# Almazny_top.net
KiCad netlist of a schematic drawn in Altium Designer
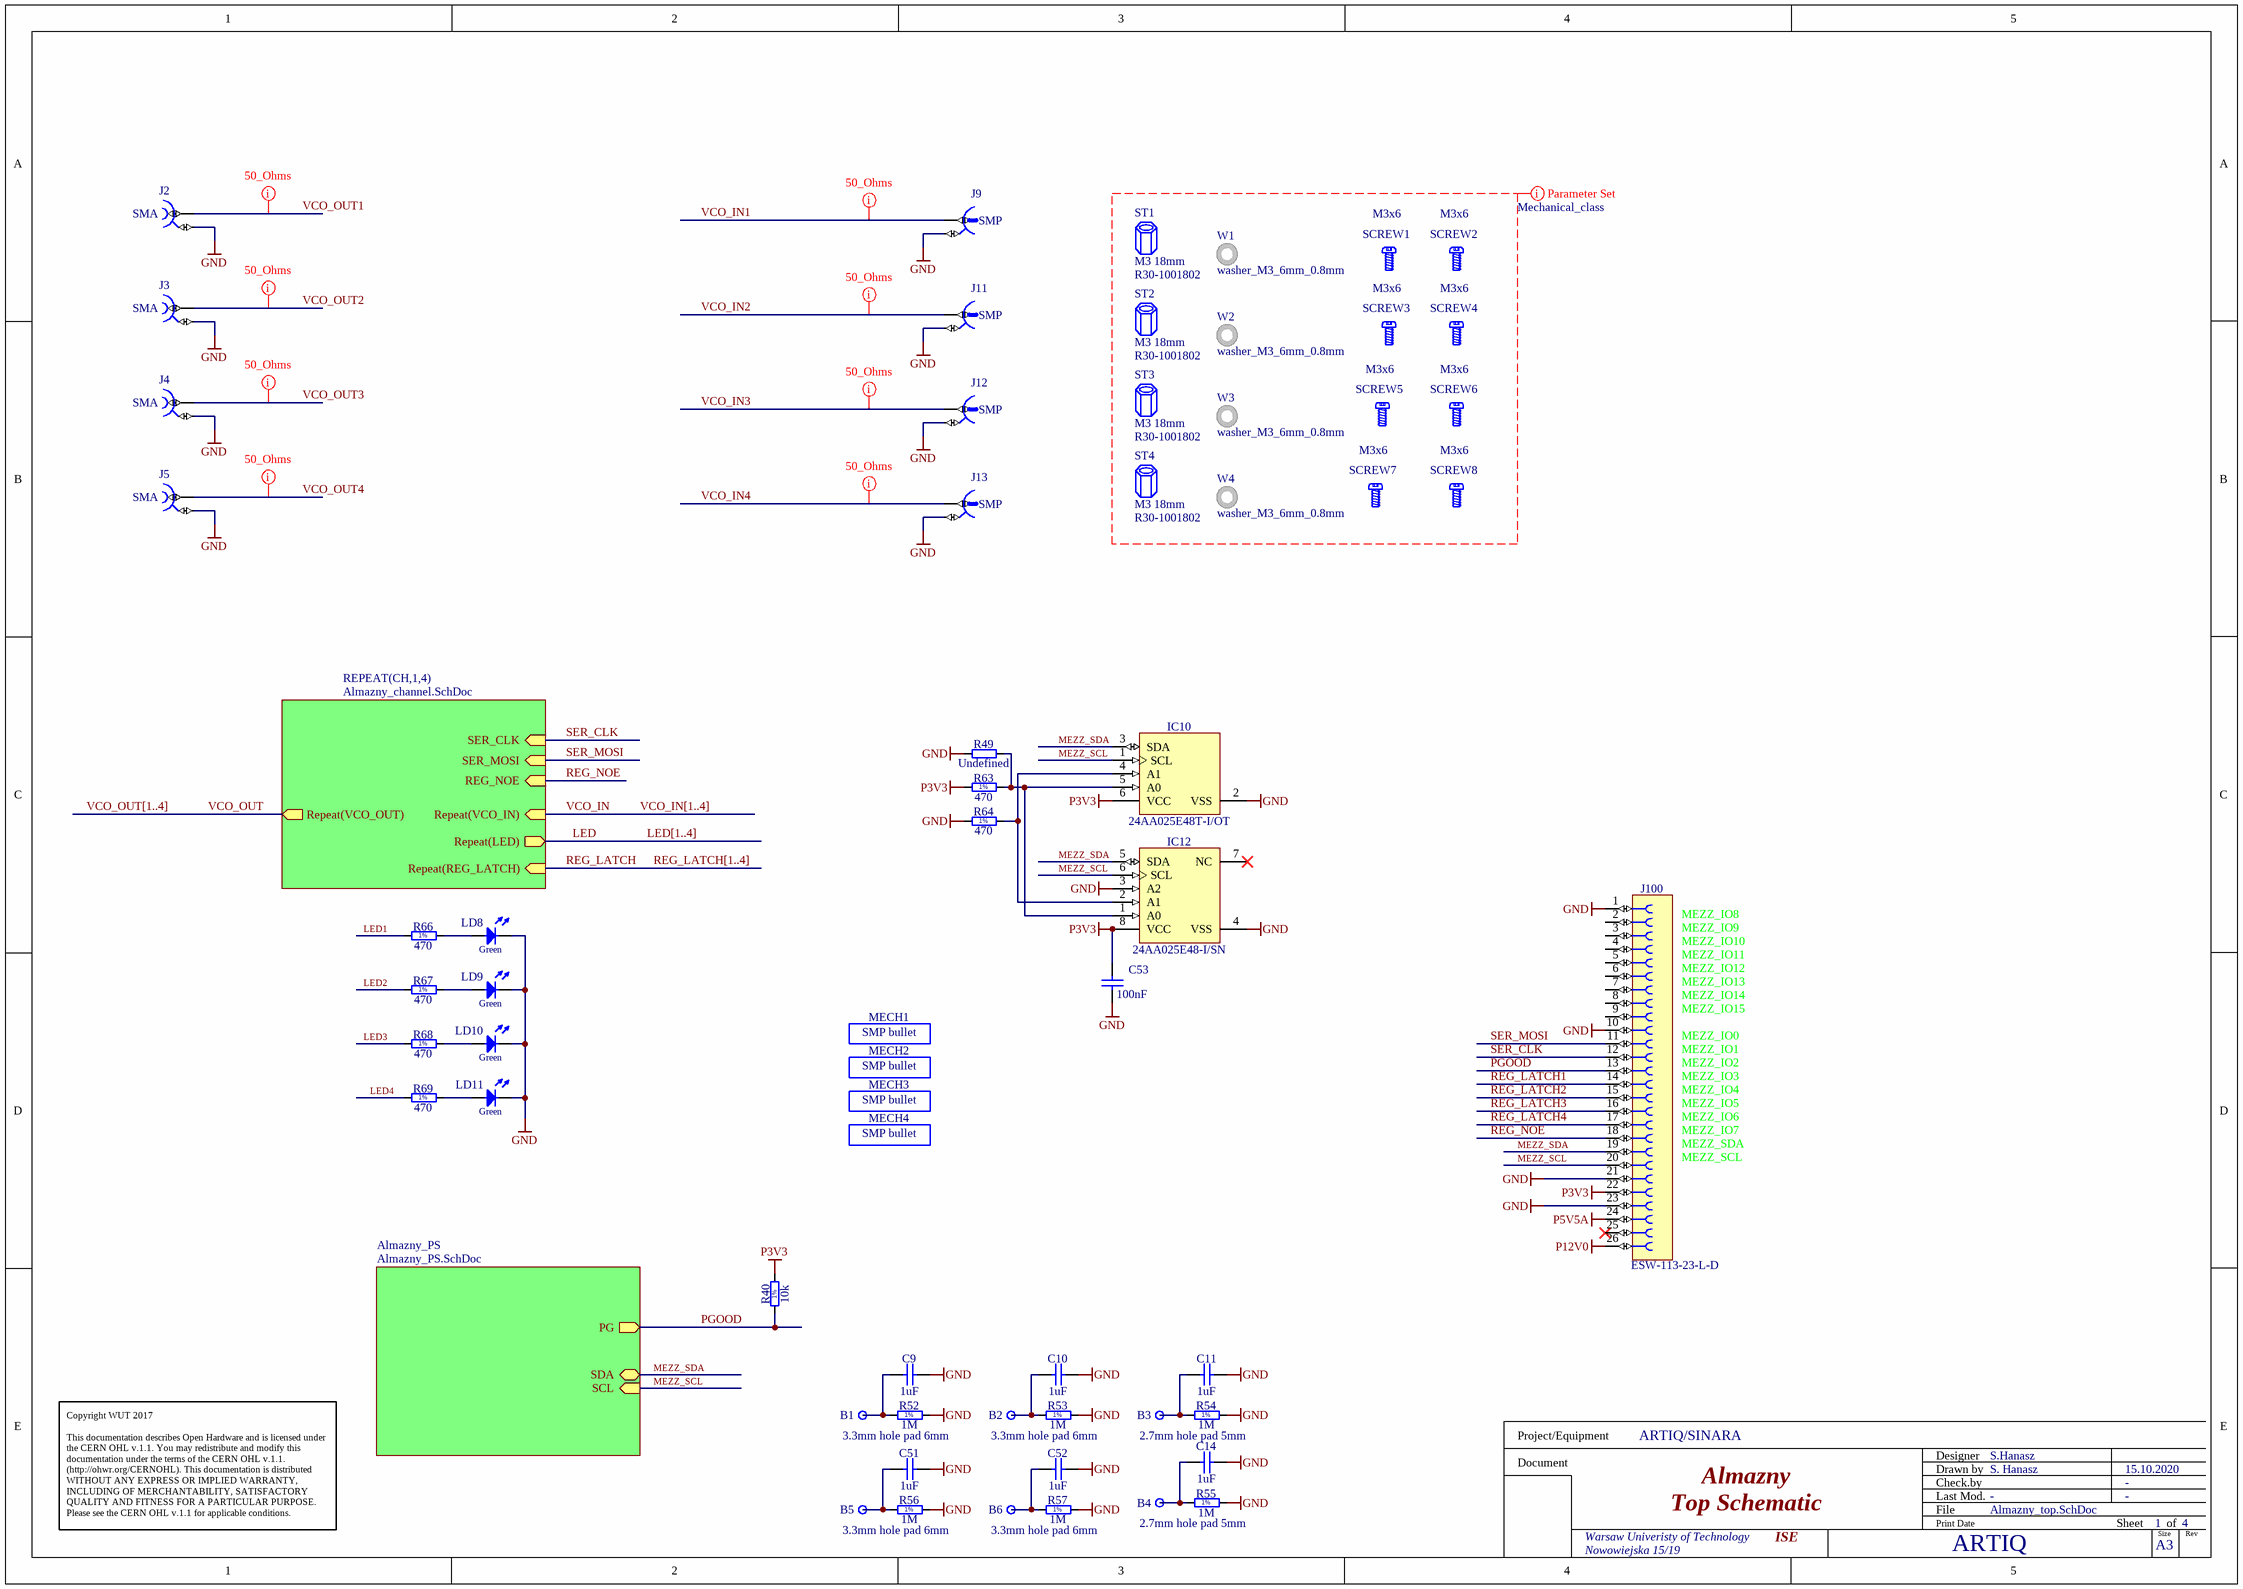
[diagram p0: Almazny_top.SchDoc]

(export (version "E")
  (design (tool "Eeschema 10.0.6"))
  (components
    (comp (ref "B1")
      (value "3.3mm hole pad 6mm")
      (footprint "MTG330_600")
      (fields (field (name "PART NUMBER") "PLATED_HOLE3.3_PAD560") (field (name "AUTHOR") "CERN DEM JMW"))
      (libsource (lib "AlmaznyLib") (part "Hole_3_3mm"))
    )
    (comp (ref "B2")
      (value "3.3mm hole pad 6mm")
      (footprint "MTG330_600")
      (fields (field (name "PART NUMBER") "PLATED_HOLE3.3_PAD560") (field (name "AUTHOR") "CERN DEM JMW"))
      (libsource (lib "AlmaznyLib") (part "Hole_3_3mm"))
    )
    (comp (ref "B3")
      (value "2.7mm hole pad 5mm")
      (footprint "MTG270_500")
      (fields (field (name "PART NUMBER") "PLATED_HOLE2.7_PAD5.0") (field (name "AUTHOR") "CERN DEM JMW"))
      (libsource (lib "AlmaznyLib") (part "Hole_2_7mm"))
    )
    (comp (ref "B4")
      (value "2.7mm hole pad 5mm")
      (footprint "MTG270_500")
      (fields (field (name "PART NUMBER") "PLATED_HOLE2.7_PAD5.0") (field (name "AUTHOR") "CERN DEM JMW"))
      (libsource (lib "AlmaznyLib") (part "Hole_2_7mm"))
    )
    (comp (ref "B5")
      (value "3.3mm hole pad 6mm")
      (footprint "MTG330_600")
      (fields (field (name "PART NUMBER") "PLATED_HOLE3.3_PAD560") (field (name "AUTHOR") "CERN DEM JMW"))
      (libsource (lib "AlmaznyLib") (part "Hole_3_3mm"))
    )
    (comp (ref "B6")
      (value "3.3mm hole pad 6mm")
      (footprint "MTG330_600")
      (fields (field (name "PART NUMBER") "PLATED_HOLE3.3_PAD560") (field (name "AUTHOR") "CERN DEM JMW"))
      (libsource (lib "AlmaznyLib") (part "Hole_3_3mm"))
    )
    (comp (ref "C9")
      (value "1uF")
      (footprint "CAPC3216X140N")
      (description "Non-polarised capacitor")
      (fields
        (field (name "PART NUMBER") "CC1206_1UF_50V_10%_X7R")
        (field (name "VOLTAGE") "50V")
        (field (name "AUTHOR") "CERN DEM JLC")
      )
      (libsource (lib "Capacitors") (part "Capacitor - non polarized"))
    )
    (comp (ref "C10")
      (value "1uF")
      (footprint "CAPC3216X140N")
      (description "Non-polarised capacitor")
      (fields
        (field (name "PART NUMBER") "CC1206_1UF_50V_10%_X7R")
        (field (name "VOLTAGE") "50V")
        (field (name "AUTHOR") "CERN DEM JLC")
      )
      (libsource (lib "Capacitors") (part "Capacitor - non polarized"))
    )
    (comp (ref "C11")
      (value "1uF")
      (footprint "CAPC3216X140N")
      (description "Non-polarised capacitor")
      (fields
        (field (name "PART NUMBER") "CC1206_1UF_50V_10%_X7R")
        (field (name "VOLTAGE") "50V")
        (field (name "AUTHOR") "CERN DEM JLC")
      )
      (libsource (lib "Capacitors") (part "Capacitor - non polarized"))
    )
    (comp (ref "C14")
      (value "1uF")
      (footprint "CAPC3216X140N")
      (description "Non-polarised capacitor")
      (fields
        (field (name "PART NUMBER") "CC1206_1UF_50V_10%_X7R")
        (field (name "VOLTAGE") "50V")
        (field (name "AUTHOR") "CERN DEM JLC")
      )
      (libsource (lib "Capacitors") (part "Capacitor - non polarized"))
    )
    (comp (ref "C51")
      (value "1uF")
      (footprint "CAPC3216X140N")
      (description "Non-polarised capacitor")
      (fields
        (field (name "PART NUMBER") "CC1206_1UF_50V_10%_X7R")
        (field (name "VOLTAGE") "50V")
        (field (name "AUTHOR") "CERN DEM JLC")
      )
      (libsource (lib "Capacitors") (part "Capacitor - non polarized"))
    )
    (comp (ref "C52")
      (value "1uF")
      (footprint "CAPC3216X140N")
      (description "Non-polarised capacitor")
      (fields
        (field (name "PART NUMBER") "CC1206_1UF_50V_10%_X7R")
        (field (name "VOLTAGE") "50V")
        (field (name "AUTHOR") "CERN DEM JLC")
      )
      (libsource (lib "Capacitors") (part "Capacitor - non polarized"))
    )
    (comp (ref "C53")
      (value "100nF")
      (footprint "CAPC1005X55N")
      (description "Non-polarised capacitor")
      (fields
        (field (name "PART NUMBER") "CC0402_100NF_16V_10%_X5R")
        (field (name "VOLTAGE") "16V")
        (field (name "AUTHOR") "CERN DEM JLC")
      )
      (libsource (lib "Capacitors") (part "Capacitor - non polarized"))
    )
    (comp (ref "IC10")
      (value "24AA025E48T-I/OT")
      (footprint "SOT95P280X145-6N")
      (description "1.7V-5.5V, 2K I2C Serial EEPROM With EUI-48 Node Identity")
      (fields (field (name "MANUFACTURER") "MICROCHIP TECHNOLOGY") (field (name "AUTHOR") "CERN DEM BC"))
      (libsource (lib "ICs And Semiconductors") (part "24AA025E48T-I/OT"))
    )
    (comp (ref "IC12")
      (value "24AA025E48-I/SN")
      (footprint "SOIC127P600X175-8N")
      (description "1.7V-5.5V, 2K I2C™ Serial EEPROMs with EUI-48™ Node Identity")
      (fields (field (name "MANUFACTURER") "MICROCHIP TECHNOLOGY") (field (name "AUTHOR") "CERN DEM MR"))
      (libsource (lib "ICs And Semiconductors") (part "24AA025E48-I/SN"))
    )
    (comp (ref "J2")
      (value "SMA")
      (footprint "TELEGARTNER_J01151A0451")
      (fields
        (field (name "PART NUMBER") "TELEGARTNER_J01151A0451")
        (field (name "MANUFACTURER") "TELEGARTNER")
        (field (name "MANUFACTURER PART NUMBER") "J01151A0451")
        (field (name "AUTHOR") "CERN DEM JLC")
      )
      (libsource (lib "Connectors") (part "Coax_1Female_1Shield"))
    )
    (comp (ref "J3")
      (value "SMA")
      (footprint "TELEGARTNER_J01151A0451")
      (fields
        (field (name "PART NUMBER") "TELEGARTNER_J01151A0451")
        (field (name "MANUFACTURER") "TELEGARTNER")
        (field (name "MANUFACTURER PART NUMBER") "J01151A0451")
        (field (name "AUTHOR") "CERN DEM JLC")
      )
      (libsource (lib "Connectors") (part "Coax_1Female_1Shield"))
    )
    (comp (ref "J4")
      (value "SMA")
      (footprint "TELEGARTNER_J01151A0451")
      (fields
        (field (name "PART NUMBER") "TELEGARTNER_J01151A0451")
        (field (name "MANUFACTURER") "TELEGARTNER")
        (field (name "MANUFACTURER PART NUMBER") "J01151A0451")
        (field (name "AUTHOR") "CERN DEM JLC")
      )
      (libsource (lib "Connectors") (part "Coax_1Female_1Shield"))
    )
    (comp (ref "J5")
      (value "SMA")
      (footprint "TELEGARTNER_J01151A0451")
      (fields
        (field (name "PART NUMBER") "TELEGARTNER_J01151A0451")
        (field (name "MANUFACTURER") "TELEGARTNER")
        (field (name "MANUFACTURER PART NUMBER") "J01151A0451")
        (field (name "AUTHOR") "CERN DEM JLC")
      )
      (libsource (lib "Connectors") (part "Coax_1Female_1Shield"))
    )
    (comp (ref "J9")
      (value "SMP")
      (footprint "MOLEX_85305-0232")
      (fields
        (field (name "PART NUMBER") "MOLEX_85305-0232")
        (field (name "MANUFACTURER") "MOLEX")
        (field (name "MANUFACTURER PART NUMBER") "85305-0232")
        (field (name "AUTHOR") "CERN DEM JMW")
      )
      (libsource (lib "Connectors") (part "Coax_1Male_1Shield"))
    )
    (comp (ref "J11")
      (value "SMP")
      (footprint "MOLEX_85305-0232")
      (fields
        (field (name "PART NUMBER") "MOLEX_85305-0232")
        (field (name "MANUFACTURER") "MOLEX")
        (field (name "MANUFACTURER PART NUMBER") "85305-0232")
        (field (name "AUTHOR") "CERN DEM JMW")
      )
      (libsource (lib "Connectors") (part "Coax_1Male_1Shield"))
    )
    (comp (ref "J12")
      (value "SMP")
      (footprint "MOLEX_85305-0232")
      (fields
        (field (name "PART NUMBER") "MOLEX_85305-0232")
        (field (name "MANUFACTURER") "MOLEX")
        (field (name "MANUFACTURER PART NUMBER") "85305-0232")
        (field (name "AUTHOR") "CERN DEM JMW")
      )
      (libsource (lib "Connectors") (part "Coax_1Male_1Shield"))
    )
    (comp (ref "J13")
      (value "SMP")
      (footprint "MOLEX_85305-0232")
      (fields
        (field (name "PART NUMBER") "MOLEX_85305-0232")
        (field (name "MANUFACTURER") "MOLEX")
        (field (name "MANUFACTURER PART NUMBER") "85305-0232")
        (field (name "AUTHOR") "CERN DEM JMW")
      )
      (libsource (lib "Connectors") (part "Coax_1Male_1Shield"))
    )
    (comp (ref "J100")
      (value "ESW-113-23-L-D")
      (footprint "ESW-113-23-L-D")
      (description "Connector Elevated Socket 26 POS 2.54mm, 13.59mm height")
      (fields
        (field (name "MANUFACTURER") "Samtec")
        (field (name "MANUFACTURER PART NUMBER") "ESW-113-23-L-D")
      )
      (libsource (lib "AlmaznyLib") (part "ESW-113-23-L-D"))
    )
    (comp (ref "LD8")
      (value "Green")
      (footprint "LED_DIALIGHT_555-230")
      (description "LED Green 1C 2A")
      (fields
        (field (name "PART NUMBER") "LED_DIALIGHT_555-2301F")
        (field (name "MANUFACTURER") "DIALIGHT")
        (field (name "AUTHOR") "CERN DEM JMW")
      )
      (libsource (lib "ICs And Semiconductors") (part "LED Green 1C 2A"))
    )
    (comp (ref "LD9")
      (value "Green")
      (footprint "LED_DIALIGHT_555-230")
      (description "LED Green 1C 2A")
      (fields
        (field (name "PART NUMBER") "LED_DIALIGHT_555-2301F")
        (field (name "MANUFACTURER") "DIALIGHT")
        (field (name "AUTHOR") "CERN DEM JMW")
      )
      (libsource (lib "ICs And Semiconductors") (part "LED Green 1C 2A"))
    )
    (comp (ref "LD10")
      (value "Green")
      (footprint "LED_DIALIGHT_555-230")
      (description "LED Green 1C 2A")
      (fields
        (field (name "PART NUMBER") "LED_DIALIGHT_555-2301F")
        (field (name "MANUFACTURER") "DIALIGHT")
        (field (name "AUTHOR") "CERN DEM JMW")
      )
      (libsource (lib "ICs And Semiconductors") (part "LED Green 1C 2A"))
    )
    (comp (ref "LD11")
      (value "Green")
      (footprint "LED_DIALIGHT_555-230")
      (description "LED Green 1C 2A")
      (fields
        (field (name "PART NUMBER") "LED_DIALIGHT_555-2301F")
        (field (name "MANUFACTURER") "DIALIGHT")
        (field (name "AUTHOR") "CERN DEM JMW")
      )
      (libsource (lib "ICs And Semiconductors") (part "LED Green 1C 2A"))
    )
    (comp (ref "MECH1")
      (value "SMP bullet")
      (footprint "GENERIC_MECH")
      (description "generic")
      (fields
        (field (name "PART NUMBER") "SMP-FS2A-1674")
        (field (name "MANUFACTURER") "AMPHENOL RF")
        (field (name "AUTHOR") "GK")
      )
      (libsource (lib "Mechanical") (part "Generic_mechanical"))
    )
    (comp (ref "MECH2")
      (value "SMP bullet")
      (footprint "GENERIC_MECH")
      (description "generic")
      (fields
        (field (name "PART NUMBER") "SMP-FS2A-1674")
        (field (name "MANUFACTURER") "AMPHENOL RF")
        (field (name "AUTHOR") "GK")
      )
      (libsource (lib "Mechanical") (part "Generic_mechanical"))
    )
    (comp (ref "MECH3")
      (value "SMP bullet")
      (footprint "GENERIC_MECH")
      (description "generic")
      (fields
        (field (name "PART NUMBER") "SMP-FS2A-1674")
        (field (name "MANUFACTURER") "AMPHENOL RF")
        (field (name "AUTHOR") "GK")
      )
      (libsource (lib "Mechanical") (part "Generic_mechanical"))
    )
    (comp (ref "MECH4")
      (value "SMP bullet")
      (footprint "GENERIC_MECH")
      (description "generic")
      (fields
        (field (name "PART NUMBER") "SMP-FS2A-1674")
        (field (name "MANUFACTURER") "AMPHENOL RF")
        (field (name "AUTHOR") "GK")
      )
      (libsource (lib "Mechanical") (part "Generic_mechanical"))
    )
    (comp (ref "R40")
      (value "10k")
      (footprint "RESC1005X40N")
      (description "Resistor - 1%")
      (fields
        (field (name "PART NUMBER") "R0402_10K_1%_0.0625W_100PPM")
        (field (name "POWER") "0.0625W")
        (field (name "AUTHOR") "CERN DEM JLC")
      )
      (libsource (lib "Resistors") (part "Resistor - 1%"))
    )
    (comp (ref "R49")
      (value "Undefined")
      (footprint "RESC1005X40N")
      (description "Resistor")
      (fields (field (name "PART NUMBER") "R0402_NO-VALUE") (field (name "AUTHOR") "CERN DEM JLC"))
      (libsource (lib "Resistors") (part "Resistor"))
    )
    (comp (ref "R52")
      (value "1M")
      (footprint "RESC1608X55N")
      (description "Resistor - 1%")
      (fields
        (field (name "PART NUMBER") "R0603_1M_1%_0.1W_100PPM")
        (field (name "POWER") "0.1W")
        (field (name "AUTHOR") "CERN DEM JLC")
      )
      (libsource (lib "Resistors") (part "Resistor - 1%"))
    )
    (comp (ref "R53")
      (value "1M")
      (footprint "RESC1608X55N")
      (description "Resistor - 1%")
      (fields
        (field (name "PART NUMBER") "R0603_1M_1%_0.1W_100PPM")
        (field (name "POWER") "0.1W")
        (field (name "AUTHOR") "CERN DEM JLC")
      )
      (libsource (lib "Resistors") (part "Resistor - 1%"))
    )
    (comp (ref "R54")
      (value "1M")
      (footprint "RESC1608X55N")
      (description "Resistor - 1%")
      (fields
        (field (name "PART NUMBER") "R0603_1M_1%_0.1W_100PPM")
        (field (name "POWER") "0.1W")
        (field (name "AUTHOR") "CERN DEM JLC")
      )
      (libsource (lib "Resistors") (part "Resistor - 1%"))
    )
    (comp (ref "R55")
      (value "1M")
      (footprint "RESC1608X55N")
      (description "Resistor - 1%")
      (fields
        (field (name "PART NUMBER") "R0603_1M_1%_0.1W_100PPM")
        (field (name "POWER") "0.1W")
        (field (name "AUTHOR") "CERN DEM JLC")
      )
      (libsource (lib "Resistors") (part "Resistor - 1%"))
    )
    (comp (ref "R56")
      (value "1M")
      (footprint "RESC1608X55N")
      (description "Resistor - 1%")
      (fields
        (field (name "PART NUMBER") "R0603_1M_1%_0.1W_100PPM")
        (field (name "POWER") "0.1W")
        (field (name "AUTHOR") "CERN DEM JLC")
      )
      (libsource (lib "Resistors") (part "Resistor - 1%"))
    )
    (comp (ref "R57")
      (value "1M")
      (footprint "RESC1608X55N")
      (description "Resistor - 1%")
      (fields
        (field (name "PART NUMBER") "R0603_1M_1%_0.1W_100PPM")
        (field (name "POWER") "0.1W")
        (field (name "AUTHOR") "CERN DEM JLC")
      )
      (libsource (lib "Resistors") (part "Resistor - 1%"))
    )
    (comp (ref "R63")
      (value "470")
      (footprint "RESC1005X40N")
      (description "Resistor - 1%")
      (fields
        (field (name "PART NUMBER") "R0402_470R_1%_0.0625W_100PPM")
        (field (name "POWER") "0.0625W")
        (field (name "AUTHOR") "CERN DEM JLC")
      )
      (libsource (lib "Resistors") (part "Resistor - 1%"))
    )
    (comp (ref "R64")
      (value "470")
      (footprint "RESC1005X40N")
      (description "Resistor - 1%")
      (fields
        (field (name "PART NUMBER") "R0402_470R_1%_0.0625W_100PPM")
        (field (name "POWER") "0.0625W")
        (field (name "AUTHOR") "CERN DEM JLC")
      )
      (libsource (lib "Resistors") (part "Resistor - 1%"))
    )
    (comp (ref "R66")
      (value "470")
      (footprint "RESC1005X40N")
      (description "Resistor - 1%")
      (fields
        (field (name "PART NUMBER") "R0402_470R_1%_0.0625W_100PPM")
        (field (name "POWER") "0.0625W")
        (field (name "AUTHOR") "CERN DEM JLC")
      )
      (libsource (lib "Resistors") (part "Resistor - 1%"))
    )
    (comp (ref "R67")
      (value "470")
      (footprint "RESC1005X40N")
      (description "Resistor - 1%")
      (fields
        (field (name "PART NUMBER") "R0402_470R_1%_0.0625W_100PPM")
        (field (name "POWER") "0.0625W")
        (field (name "AUTHOR") "CERN DEM JLC")
      )
      (libsource (lib "Resistors") (part "Resistor - 1%"))
    )
    (comp (ref "R68")
      (value "470")
      (footprint "RESC1005X40N")
      (description "Resistor - 1%")
      (fields
        (field (name "PART NUMBER") "R0402_470R_1%_0.0625W_100PPM")
        (field (name "POWER") "0.0625W")
        (field (name "AUTHOR") "CERN DEM JLC")
      )
      (libsource (lib "Resistors") (part "Resistor - 1%"))
    )
    (comp (ref "R69")
      (value "470")
      (footprint "RESC1005X40N")
      (description "Resistor - 1%")
      (fields
        (field (name "PART NUMBER") "R0402_470R_1%_0.0625W_100PPM")
        (field (name "POWER") "0.0625W")
        (field (name "AUTHOR") "CERN DEM JLC")
      )
      (libsource (lib "Resistors") (part "Resistor - 1%"))
    )
    (comp (ref "SCREW1")
      (value "M3x6")
      (footprint "BOSSARD_BN9524-3271397_v")
      (description "Screw")
      (fields
        (field (name "PART NUMBER") "BOSSARD_BN9524-3271397_v")
        (field (name "MANUFACTURER") "BOSSARD")
        (field (name "AUTHOR") "CERN DEM JLC")
      )
      (libsource (lib "Eletro-mechanical") (part "Screw"))
    )
    (comp (ref "SCREW2")
      (value "M3x6")
      (footprint "BOSSARD_BN9524-3271397_v")
      (description "Screw")
      (fields
        (field (name "PART NUMBER") "BOSSARD_BN9524-3271397_v")
        (field (name "MANUFACTURER") "BOSSARD")
        (field (name "AUTHOR") "CERN DEM JLC")
      )
      (libsource (lib "Eletro-mechanical") (part "Screw"))
    )
    (comp (ref "SCREW3")
      (value "M3x6")
      (footprint "BOSSARD_BN9524-3271397_v")
      (description "Screw")
      (fields
        (field (name "PART NUMBER") "BOSSARD_BN9524-3271397_v")
        (field (name "MANUFACTURER") "BOSSARD")
        (field (name "AUTHOR") "CERN DEM JLC")
      )
      (libsource (lib "Eletro-mechanical") (part "Screw"))
    )
    (comp (ref "SCREW4")
      (value "M3x6")
      (footprint "BOSSARD_BN9524-3271397_v")
      (description "Screw")
      (fields
        (field (name "PART NUMBER") "BOSSARD_BN9524-3271397_v")
        (field (name "MANUFACTURER") "BOSSARD")
        (field (name "AUTHOR") "CERN DEM JLC")
      )
      (libsource (lib "Eletro-mechanical") (part "Screw"))
    )
    (comp (ref "SCREW5")
      (value "M3x6")
      (footprint "BOSSARD_BN9524-3271397_v")
      (description "Screw")
      (fields
        (field (name "PART NUMBER") "BOSSARD_BN9524-3271397_v")
        (field (name "MANUFACTURER") "BOSSARD")
        (field (name "AUTHOR") "CERN DEM JLC")
      )
      (libsource (lib "Eletro-mechanical") (part "Screw"))
    )
    (comp (ref "SCREW6")
      (value "M3x6")
      (footprint "BOSSARD_BN9524-3271397_v")
      (description "Screw")
      (fields
        (field (name "PART NUMBER") "BOSSARD_BN9524-3271397_v")
        (field (name "MANUFACTURER") "BOSSARD")
        (field (name "AUTHOR") "CERN DEM JLC")
      )
      (libsource (lib "Eletro-mechanical") (part "Screw"))
    )
    (comp (ref "SCREW7")
      (value "M3x6")
      (footprint "BOSSARD_BN9524-3271397_v")
      (description "Screw")
      (fields
        (field (name "PART NUMBER") "BOSSARD_BN9524-3271397_v")
        (field (name "MANUFACTURER") "BOSSARD")
        (field (name "AUTHOR") "CERN DEM JLC")
      )
      (libsource (lib "Eletro-mechanical") (part "Screw"))
    )
    (comp (ref "SCREW8")
      (value "M3x6")
      (footprint "BOSSARD_BN9524-3271397_v")
      (description "Screw")
      (fields
        (field (name "PART NUMBER") "BOSSARD_BN9524-3271397_v")
        (field (name "MANUFACTURER") "BOSSARD")
        (field (name "AUTHOR") "CERN DEM JLC")
      )
      (libsource (lib "Eletro-mechanical") (part "Screw"))
    )
    (comp (ref "ST1")
      (value "M3 18mm")
      (footprint "R30-1001802")
      (description "M3.0x18 standoff")
      (fields (field (name "MANUFACTURER") "Harwin") (field (name "MANUFACTURER PART NUMBER") "R30-1001802"))
      (libsource (lib "mechanical") (part "STANDOFF_HARWIN_R30_1001802"))
    )
    (comp (ref "ST2")
      (value "M3 18mm")
      (footprint "R30-1001802")
      (description "M3.0x18 standoff")
      (fields (field (name "MANUFACTURER") "Harwin") (field (name "MANUFACTURER PART NUMBER") "R30-1001802"))
      (libsource (lib "mechanical") (part "STANDOFF_HARWIN_R30_1001802"))
    )
    (comp (ref "ST3")
      (value "M3 18mm")
      (footprint "R30-1001802")
      (description "M3.0x18 standoff")
      (fields (field (name "MANUFACTURER") "Harwin") (field (name "MANUFACTURER PART NUMBER") "R30-1001802"))
      (libsource (lib "mechanical") (part "STANDOFF_HARWIN_R30_1001802"))
    )
    (comp (ref "ST4")
      (value "M3 18mm")
      (footprint "R30-1001802")
      (description "M3.0x18 standoff")
      (fields (field (name "MANUFACTURER") "Harwin") (field (name "MANUFACTURER PART NUMBER") "R30-1001802"))
      (libsource (lib "mechanical") (part "STANDOFF_HARWIN_R30_1001802"))
    )
    (comp (ref "W1")
      (value "washer_M3_6mm_0.8mm")
      (footprint "washer_M3_6mm_0.8mm")
      (description "M3 Washer:\r\nID: 3.2mm\r\nOD: 6mm\r\nThickness 0.8mm")
      (fields
        (field (name "MANUFACTURER") "Accu Limited")
        (field (name "MANUFACTURER PART NUMBER") "HAFZ-M3-A4")
      )
      (libsource (lib "mechanical") (part "washer_M3_6mm_0.8mm"))
    )
    (comp (ref "W2")
      (value "washer_M3_6mm_0.8mm")
      (footprint "washer_M3_6mm_0.8mm")
      (description "M3 Washer:\r\nID: 3.2mm\r\nOD: 6mm\r\nThickness 0.8mm")
      (fields
        (field (name "MANUFACTURER") "Accu Limited")
        (field (name "MANUFACTURER PART NUMBER") "HAFZ-M3-A4")
      )
      (libsource (lib "mechanical") (part "washer_M3_6mm_0.8mm"))
    )
    (comp (ref "W3")
      (value "washer_M3_6mm_0.8mm")
      (footprint "washer_M3_6mm_0.8mm")
      (description "M3 Washer:\r\nID: 3.2mm\r\nOD: 6mm\r\nThickness 0.8mm")
      (fields
        (field (name "MANUFACTURER") "Accu Limited")
        (field (name "MANUFACTURER PART NUMBER") "HAFZ-M3-A4")
      )
      (libsource (lib "mechanical") (part "washer_M3_6mm_0.8mm"))
    )
    (comp (ref "W4")
      (value "washer_M3_6mm_0.8mm")
      (footprint "washer_M3_6mm_0.8mm")
      (description "M3 Washer:\r\nID: 3.2mm\r\nOD: 6mm\r\nThickness 0.8mm")
      (fields
        (field (name "MANUFACTURER") "Accu Limited")
        (field (name "MANUFACTURER PART NUMBER") "HAFZ-M3-A4")
      )
      (libsource (lib "mechanical") (part "washer_M3_6mm_0.8mm"))
    )
  )
  (nets
    (net (code "2") (name "/LED1") (class "Default")
      (node (ref "R66") (pin "1") (pinfunction "1_1") (pintype "passive"))
    )
    (net (code "3") (name "/LED2") (class "Default")
      (node (ref "R67") (pin "1") (pinfunction "1_1") (pintype "passive"))
    )
    (net (code "4") (name "/LED3") (class "Default")
      (node (ref "R68") (pin "1") (pinfunction "1_1") (pintype "passive"))
    )
    (net (code "5") (name "/LED4") (class "Default")
      (node (ref "R69") (pin "1") (pinfunction "1_1") (pintype "passive"))
    )
    (net (code "7") (name "/MEZZ_SCL") (class "Default")
      (node (ref "IC10") (pin "1") (pinfunction "SCL_1") (pintype "input"))
      (node (ref "IC12") (pin "6") (pinfunction "SCL_6") (pintype "input"))
      (node (ref "J100") (pin "20") (pinfunction "20_20") (pintype "bidirectional"))
    )
    (net (code "8") (name "/MEZZ_SDA") (class "Default")
      (node (ref "IC10") (pin "3") (pinfunction "SDA_3") (pintype "bidirectional"))
      (node (ref "IC12") (pin "5") (pinfunction "SDA_5") (pintype "bidirectional"))
      (node (ref "J100") (pin "19") (pinfunction "19_19") (pintype "bidirectional"))
    )
    (net (code "9") (name "/PGOOD") (class "Default")
      (node (ref "J100") (pin "13") (pinfunction "13_13") (pintype "bidirectional"))
      (node (ref "R40") (pin "1") (pinfunction "1_1") (pintype "passive"))
    )
    (net (code "11") (name "/REG_LATCH1") (class "Default")
      (node (ref "J100") (pin "14") (pinfunction "14_14") (pintype "bidirectional"))
    )
    (net (code "12") (name "/REG_LATCH2") (class "Default")
      (node (ref "J100") (pin "15") (pinfunction "15_15") (pintype "bidirectional"))
    )
    (net (code "13") (name "/REG_LATCH3") (class "Default")
      (node (ref "J100") (pin "16") (pinfunction "16_16") (pintype "bidirectional"))
    )
    (net (code "14") (name "/REG_LATCH4") (class "Default")
      (node (ref "J100") (pin "17") (pinfunction "17_17") (pintype "bidirectional"))
    )
    (net (code "16") (name "/REG_NOE") (class "Default")
      (node (ref "J100") (pin "18") (pinfunction "18_18") (pintype "bidirectional"))
    )
    (net (code "17") (name "/SER_CLK") (class "Default")
      (node (ref "J100") (pin "12") (pinfunction "12_12") (pintype "bidirectional"))
    )
    (net (code "18") (name "/SER_MOSI") (class "Default")
      (node (ref "J100") (pin "11") (pinfunction "11_11") (pintype "bidirectional"))
    )
    (net (code "20") (name "/VCO_IN1") (class "Default")
      (node (ref "J9") (pin "1") (pinfunction "1_1") (pintype "bidirectional"))
    )
    (net (code "21") (name "/VCO_IN2") (class "Default")
      (node (ref "J11") (pin "1") (pinfunction "1_1") (pintype "bidirectional"))
    )
    (net (code "22") (name "/VCO_IN3") (class "Default")
      (node (ref "J12") (pin "1") (pinfunction "1_1") (pintype "bidirectional"))
    )
    (net (code "23") (name "/VCO_IN4") (class "Default")
      (node (ref "J13") (pin "1") (pinfunction "1_1") (pintype "bidirectional"))
    )
    (net (code "26") (name "/VCO_OUT1") (class "Default")
      (node (ref "J2") (pin "1") (pinfunction "1_1") (pintype "bidirectional"))
    )
    (net (code "27") (name "/VCO_OUT2") (class "Default")
      (node (ref "J3") (pin "1") (pinfunction "1_1") (pintype "bidirectional"))
    )
    (net (code "28") (name "/VCO_OUT3") (class "Default")
      (node (ref "J4") (pin "1") (pinfunction "1_1") (pintype "bidirectional"))
    )
    (net (code "29") (name "/VCO_OUT4") (class "Default")
      (node (ref "J5") (pin "1") (pinfunction "1_1") (pintype "bidirectional"))
    )
    (net (code "31") (name "GND") (class "Default")
      (node (ref "C10") (pin "2") (pinfunction "2_2") (pintype "passive"))
      (node (ref "C11") (pin "2") (pinfunction "2_2") (pintype "passive"))
      (node (ref "C14") (pin "2") (pinfunction "2_2") (pintype "passive"))
      (node (ref "C51") (pin "2") (pinfunction "2_2") (pintype "passive"))
      (node (ref "C52") (pin "2") (pinfunction "2_2") (pintype "passive"))
      (node (ref "C53") (pin "1") (pinfunction "1_1") (pintype "passive"))
      (node (ref "C9") (pin "2") (pinfunction "2_2") (pintype "passive"))
      (node (ref "IC10") (pin "2") (pinfunction "VSS_2") (pintype "power_in"))
      (node (ref "IC12") (pin "3") (pinfunction "A2_3") (pintype "input"))
      (node (ref "IC12") (pin "4") (pinfunction "VSS_4") (pintype "power_in"))
      (node (ref "J100") (pin "1") (pinfunction "1_1") (pintype "bidirectional"))
      (node (ref "J100") (pin "10") (pinfunction "10_10") (pintype "bidirectional"))
      (node (ref "J100") (pin "21") (pinfunction "21_21") (pintype "bidirectional"))
      (node (ref "J100") (pin "23") (pinfunction "23_23") (pintype "bidirectional"))
      (node (ref "J11") (pin "2") (pinfunction "2_2") (pintype "bidirectional"))
      (node (ref "J12") (pin "2") (pinfunction "2_2") (pintype "bidirectional"))
      (node (ref "J13") (pin "2") (pinfunction "2_2") (pintype "bidirectional"))
      (node (ref "J2") (pin "2") (pinfunction "2_2") (pintype "bidirectional"))
      (node (ref "J3") (pin "2") (pinfunction "2_2") (pintype "bidirectional"))
      (node (ref "J4") (pin "2") (pinfunction "2_2") (pintype "bidirectional"))
      (node (ref "J5") (pin "2") (pinfunction "2_2") (pintype "bidirectional"))
      (node (ref "J9") (pin "2") (pinfunction "2_2") (pintype "bidirectional"))
      (node (ref "LD10") (pin "1") (pinfunction "C_1") (pintype "passive"))
      (node (ref "LD11") (pin "1") (pinfunction "C_1") (pintype "passive"))
      (node (ref "LD8") (pin "1") (pinfunction "C_1") (pintype "passive"))
      (node (ref "LD9") (pin "1") (pinfunction "C_1") (pintype "passive"))
      (node (ref "R49") (pin "1") (pinfunction "1_1") (pintype "passive"))
      (node (ref "R52") (pin "2") (pinfunction "2_2") (pintype "passive"))
      (node (ref "R53") (pin "2") (pinfunction "2_2") (pintype "passive"))
      (node (ref "R54") (pin "2") (pinfunction "2_2") (pintype "passive"))
      (node (ref "R55") (pin "2") (pinfunction "2_2") (pintype "passive"))
      (node (ref "R56") (pin "2") (pinfunction "2_2") (pintype "passive"))
      (node (ref "R57") (pin "2") (pinfunction "2_2") (pintype "passive"))
      (node (ref "R64") (pin "1") (pinfunction "1_1") (pintype "passive"))
    )
    (net (code "32") (name "Net-(B1-Pad1)") (class "Default")
      (node (ref "B1") (pin "1") (pinfunction "1_1") (pintype "bidirectional"))
      (node (ref "C9") (pin "1") (pinfunction "1_1") (pintype "passive"))
      (node (ref "R52") (pin "1") (pinfunction "1_1") (pintype "passive"))
    )
    (net (code "33") (name "Net-(B2-Pad1)") (class "Default")
      (node (ref "B2") (pin "1") (pinfunction "1_1") (pintype "bidirectional"))
      (node (ref "C10") (pin "1") (pinfunction "1_1") (pintype "passive"))
      (node (ref "R53") (pin "1") (pinfunction "1_1") (pintype "passive"))
    )
    (net (code "34") (name "Net-(B3-Pad1)") (class "Default")
      (node (ref "B3") (pin "1") (pinfunction "1_1") (pintype "bidirectional"))
      (node (ref "C11") (pin "1") (pinfunction "1_1") (pintype "passive"))
      (node (ref "R54") (pin "1") (pinfunction "1_1") (pintype "passive"))
    )
    (net (code "35") (name "Net-(B4-Pad1)") (class "Default")
      (node (ref "B4") (pin "1") (pinfunction "1_1") (pintype "bidirectional"))
      (node (ref "C14") (pin "1") (pinfunction "1_1") (pintype "passive"))
      (node (ref "R55") (pin "1") (pinfunction "1_1") (pintype "passive"))
    )
    (net (code "36") (name "Net-(B5-Pad1)") (class "Default")
      (node (ref "B5") (pin "1") (pinfunction "1_1") (pintype "bidirectional"))
      (node (ref "C51") (pin "1") (pinfunction "1_1") (pintype "passive"))
      (node (ref "R56") (pin "1") (pinfunction "1_1") (pintype "passive"))
    )
    (net (code "37") (name "Net-(B6-Pad1)") (class "Default")
      (node (ref "B6") (pin "1") (pinfunction "1_1") (pintype "bidirectional"))
      (node (ref "C52") (pin "1") (pinfunction "1_1") (pintype "passive"))
      (node (ref "R57") (pin "1") (pinfunction "1_1") (pintype "passive"))
    )
    (net (code "38") (name "Net-(IC10-A0)") (class "Default")
      (node (ref "IC10") (pin "5") (pinfunction "A0_5") (pintype "input"))
      (node (ref "IC12") (pin "1") (pinfunction "A0_1") (pintype "input"))
      (node (ref "R49") (pin "2") (pinfunction "2_2") (pintype "passive"))
      (node (ref "R63") (pin "2") (pinfunction "2_2") (pintype "passive"))
    )
    (net (code "39") (name "Net-(IC10-A1)") (class "Default")
      (node (ref "IC10") (pin "4") (pinfunction "A1_4") (pintype "input"))
      (node (ref "IC12") (pin "2") (pinfunction "A1_2") (pintype "input"))
      (node (ref "R64") (pin "2") (pinfunction "2_2") (pintype "passive"))
    )
    (net (code "40") (name "Net-(LD8-A)") (class "Default")
      (node (ref "LD8") (pin "2") (pinfunction "A_2") (pintype "passive"))
      (node (ref "R66") (pin "2") (pinfunction "2_2") (pintype "passive"))
    )
    (net (code "41") (name "Net-(LD9-A)") (class "Default")
      (node (ref "LD9") (pin "2") (pinfunction "A_2") (pintype "passive"))
      (node (ref "R67") (pin "2") (pinfunction "2_2") (pintype "passive"))
    )
    (net (code "42") (name "Net-(LD10-A)") (class "Default")
      (node (ref "LD10") (pin "2") (pinfunction "A_2") (pintype "passive"))
      (node (ref "R68") (pin "2") (pinfunction "2_2") (pintype "passive"))
    )
    (net (code "43") (name "Net-(LD11-A)") (class "Default")
      (node (ref "LD11") (pin "2") (pinfunction "A_2") (pintype "passive"))
      (node (ref "R69") (pin "2") (pinfunction "2_2") (pintype "passive"))
    )
    (net (code "44") (name "P3V3") (class "Default")
      (node (ref "C53") (pin "2") (pinfunction "2_2") (pintype "passive"))
      (node (ref "IC10") (pin "6") (pinfunction "VCC_6") (pintype "power_in"))
      (node (ref "IC12") (pin "8") (pinfunction "VCC_8") (pintype "power_in"))
      (node (ref "J100") (pin "22") (pinfunction "22_22") (pintype "bidirectional"))
      (node (ref "R40") (pin "2") (pinfunction "2_2") (pintype "passive"))
      (node (ref "R63") (pin "1") (pinfunction "1_1") (pintype "passive"))
    )
    (net (code "45") (name "P5V5A") (class "Default")
      (node (ref "J100") (pin "24") (pinfunction "24_24") (pintype "bidirectional"))
    )
    (net (code "46") (name "P12V0") (class "Default")
      (node (ref "J100") (pin "26") (pinfunction "26_26") (pintype "bidirectional"))
    )
    (net (code "47") (name "unconnected-(IC12-NC-Pad7)") (class "Default")
      (node (ref "IC12") (pin "7") (pinfunction "NC_7") (pintype "passive+no_connect"))
    )
    (net (code "48") (name "unconnected-(J100-Pad2)") (class "Default")
      (node (ref "J100") (pin "2") (pinfunction "2_2") (pintype "bidirectional"))
    )
    (net (code "49") (name "unconnected-(J100-Pad3)") (class "Default")
      (node (ref "J100") (pin "3") (pinfunction "3_3") (pintype "bidirectional"))
    )
    (net (code "50") (name "unconnected-(J100-Pad4)") (class "Default")
      (node (ref "J100") (pin "4") (pinfunction "4_4") (pintype "bidirectional"))
    )
    (net (code "51") (name "unconnected-(J100-Pad5)") (class "Default")
      (node (ref "J100") (pin "5") (pinfunction "5_5") (pintype "bidirectional"))
    )
    (net (code "52") (name "unconnected-(J100-Pad6)") (class "Default")
      (node (ref "J100") (pin "6") (pinfunction "6_6") (pintype "bidirectional"))
    )
    (net (code "53") (name "unconnected-(J100-Pad7)") (class "Default")
      (node (ref "J100") (pin "7") (pinfunction "7_7") (pintype "bidirectional"))
    )
    (net (code "54") (name "unconnected-(J100-Pad8)") (class "Default")
      (node (ref "J100") (pin "8") (pinfunction "8_8") (pintype "bidirectional"))
    )
    (net (code "55") (name "unconnected-(J100-Pad9)") (class "Default")
      (node (ref "J100") (pin "9") (pinfunction "9_9") (pintype "bidirectional"))
    )
    (net (code "56") (name "unconnected-(J100-Pad25)") (class "Default")
      (node (ref "J100") (pin "25") (pinfunction "25_25") (pintype "bidirectional+no_connect"))
    )
  )
)
